# SHASwitch1.net
KiCad netlist of a schematic drawn in EAGLE
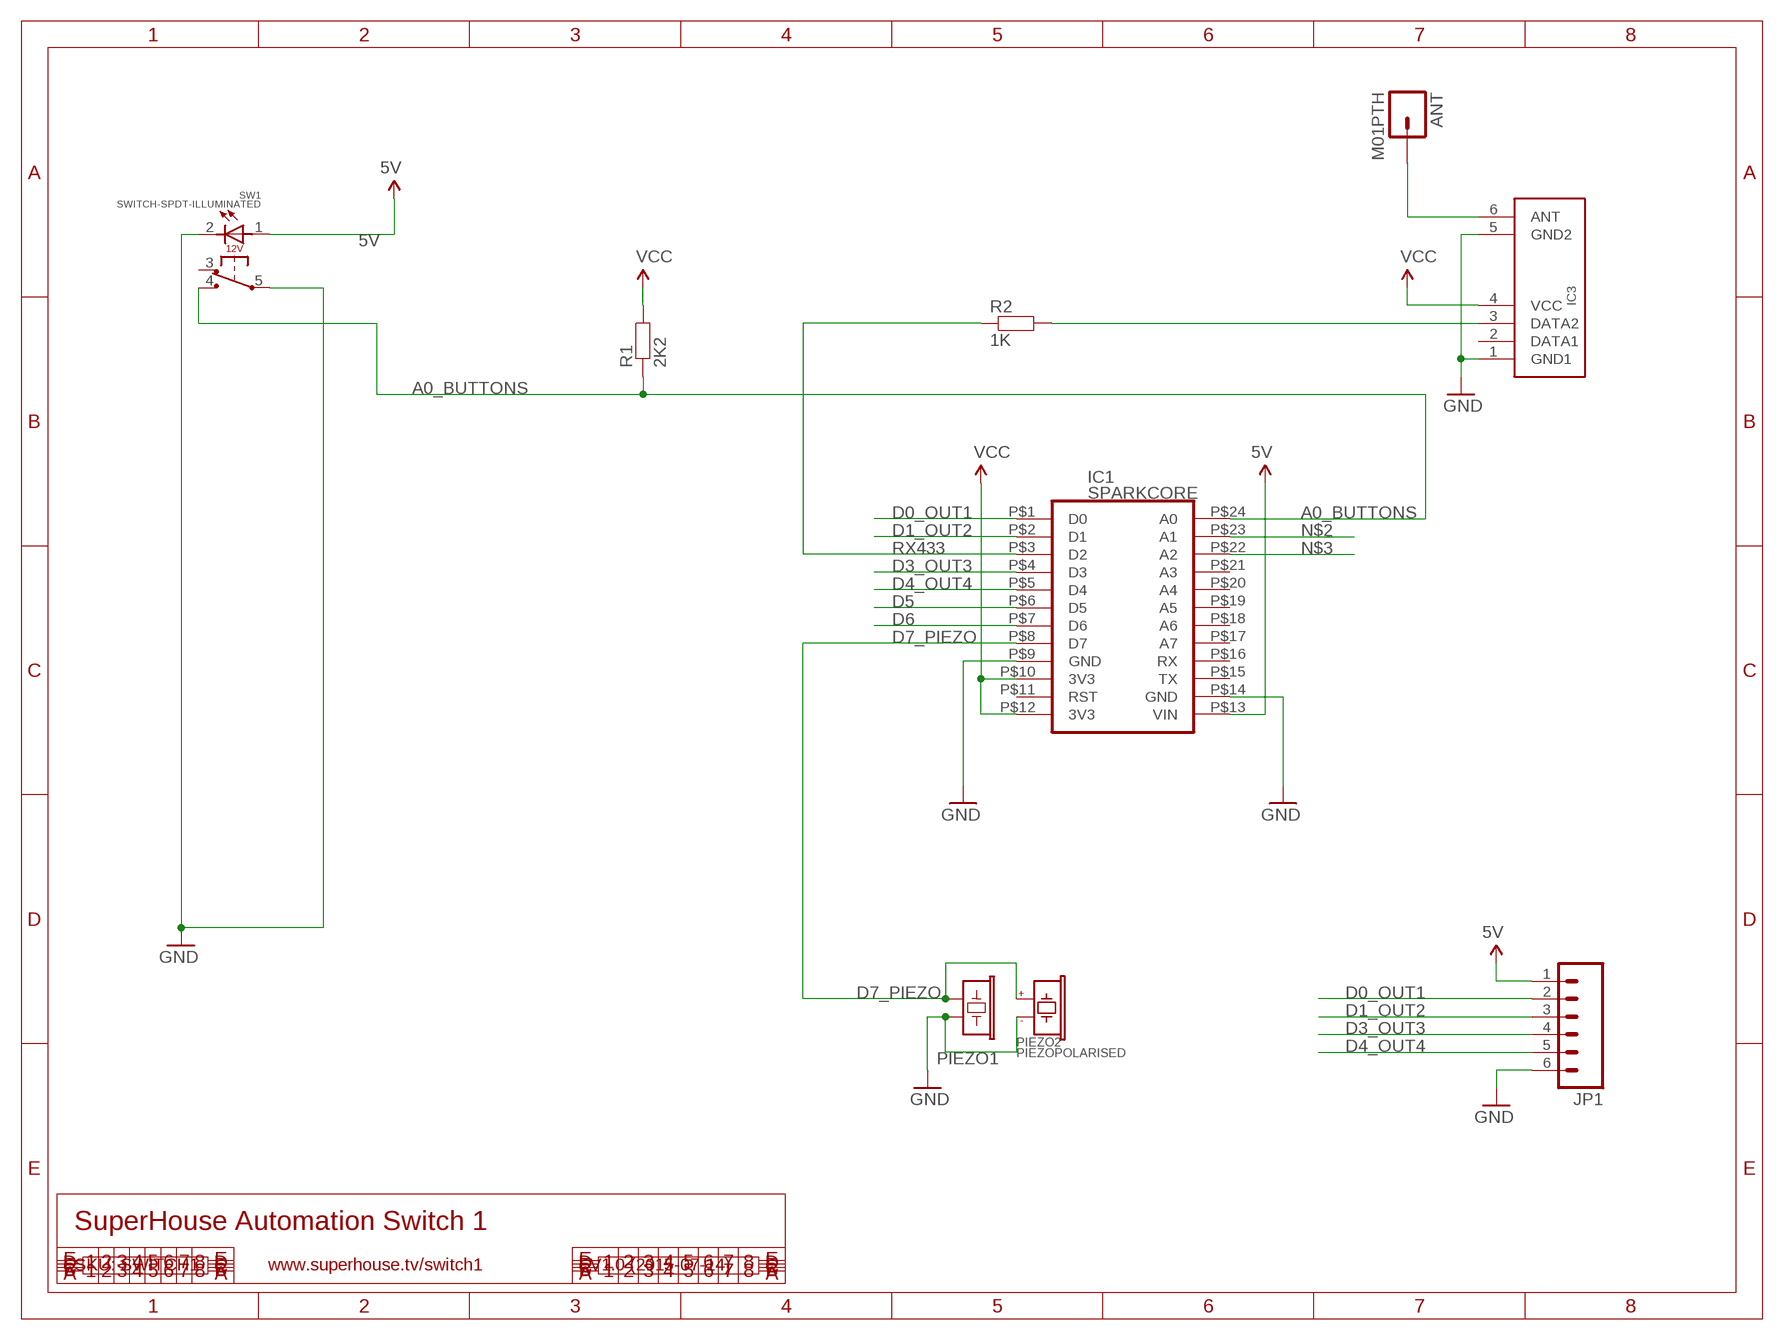
[diagram p0: schematic, sheet 1]

(export (version "E")
  (design (tool "Eeschema 10.0.6"))
  (components
    (comp (ref "ANT")
      (value "M01PTH")
      (footprint "eagle-import:1X01")
      (libsource (lib "eagle-import") (part "M01PTH"))
    )
    (comp (ref "IC1")
      (value "SPARKCORE")
      (footprint "eagle-import:SPARKCORE")
      (libsource (lib "eagle-import") (part "SPARKCORE"))
    )
    (comp (ref "IC3")
      (value "RXB1")
      (footprint "eagle-import:RX-B1-SHORT-FLAT")
      (libsource (lib "eagle-import") (part "RXB1SHORTFLAT"))
    )
    (comp (ref "JP1")
      (value "M06SIP")
      (footprint "eagle-import:1X06")
      (libsource (lib "eagle-import") (part "M06SIP"))
    )
    (comp (ref "PIEZO1")
      (value "BUZZERSMD12X12")
      (footprint "eagle-import:BUZZER-12X12-SMT")
      (libsource (lib "eagle-import") (part "BUZZERSMD12X12"))
    )
    (comp (ref "PIEZO2")
      (value "PIEZOPOLARISED")
      (footprint "eagle-import:PIEZO12MMWIDEPOLARISED")
      (libsource (lib "eagle-import") (part "PIEZOPOLARISED"))
    )
    (comp (ref "R1")
      (value "2K2")
      (footprint "eagle-import:0603")
      (libsource (lib "eagle-import") (part "RESISTOR0603"))
    )
    (comp (ref "R2")
      (value "1K")
      (footprint "eagle-import:0603")
      (libsource (lib "eagle-import") (part "RESISTOR0603"))
    )
    (comp (ref "SW1")
      (value "SWITCH-SPDT-ILLUMINATED")
      (footprint "eagle-import:SWITCH-SPDT-ILLUMINATED")
      (libsource (lib "eagle-import") (part "SWITCH-SPDT-ILLUMINATED"))
    )
  )
  (nets
    (net (code "1") (name "/A0_BUTTONS") (class "Default")
      (node (ref "IC1") (pin "P$24") (pinfunction "A0_P$24") (pintype "bidirectional"))
      (node (ref "R1") (pin "1") (pinfunction "1_1") (pintype "passive"))
      (node (ref "SW1") (pin "4") (pinfunction "NO_4") (pintype "passive"))
    )
    (net (code "2") (name "/D0_OUT1") (class "Default")
      (node (ref "IC1") (pin "P$1") (pinfunction "D0_P$1") (pintype "bidirectional"))
      (node (ref "JP1") (pin "2") (pinfunction "2_2") (pintype "passive"))
    )
    (net (code "3") (name "/D1_OUT2") (class "Default")
      (node (ref "IC1") (pin "P$2") (pinfunction "D1_P$2") (pintype "bidirectional"))
      (node (ref "JP1") (pin "3") (pinfunction "3_3") (pintype "passive"))
    )
    (net (code "4") (name "/D3_OUT3") (class "Default")
      (node (ref "IC1") (pin "P$4") (pinfunction "D3_P$4") (pintype "bidirectional"))
      (node (ref "JP1") (pin "4") (pinfunction "4_4") (pintype "passive"))
    )
    (net (code "5") (name "/D4_OUT4") (class "Default")
      (node (ref "IC1") (pin "P$5") (pinfunction "D4_P$5") (pintype "bidirectional"))
      (node (ref "JP1") (pin "5") (pinfunction "5_5") (pintype "passive"))
    )
    (net (code "6") (name "/D5") (class "Default")
      (node (ref "IC1") (pin "P$6") (pinfunction "D5_P$6") (pintype "bidirectional"))
    )
    (net (code "7") (name "/D6") (class "Default")
      (node (ref "IC1") (pin "P$7") (pinfunction "D6_P$7") (pintype "bidirectional"))
    )
    (net (code "8") (name "/D7_PIEZO") (class "Default")
      (node (ref "IC1") (pin "P$8") (pinfunction "D7_P$8") (pintype "bidirectional"))
      (node (ref "PIEZO1") (pin "1") (pinfunction "1_1") (pintype "passive"))
      (node (ref "PIEZO2") (pin "1") (pinfunction "+_1") (pintype "bidirectional"))
    )
    (net (code "9") (name "/N$2") (class "Default")
      (node (ref "IC1") (pin "P$23") (pinfunction "A1_P$23") (pintype "bidirectional"))
    )
    (net (code "10") (name "/N$3") (class "Default")
      (node (ref "IC1") (pin "P$22") (pinfunction "A2_P$22") (pintype "bidirectional"))
    )
    (net (code "11") (name "/RX433") (class "Default")
      (node (ref "IC1") (pin "P$3") (pinfunction "D2_P$3") (pintype "bidirectional"))
      (node (ref "R2") (pin "1") (pinfunction "1_1") (pintype "passive"))
    )
    (net (code "12") (name "5V") (class "Default")
      (node (ref "IC1") (pin "P$13") (pinfunction "VIN_P$13") (pintype "bidirectional"))
      (node (ref "JP1") (pin "1") (pinfunction "1_1") (pintype "passive"))
      (node (ref "SW1") (pin "1") (pinfunction "+_1") (pintype "passive"))
    )
    (net (code "13") (name "GND") (class "Default")
      (node (ref "IC1") (pin "P$14") (pinfunction "GND_P$14") (pintype "bidirectional"))
      (node (ref "IC1") (pin "P$9") (pinfunction "GND_P$9") (pintype "bidirectional"))
      (node (ref "IC3") (pin "1") (pinfunction "GND1_1") (pintype "bidirectional"))
      (node (ref "IC3") (pin "5") (pinfunction "GND2_5") (pintype "bidirectional"))
      (node (ref "JP1") (pin "6") (pinfunction "6_6") (pintype "passive"))
      (node (ref "PIEZO1") (pin "2") (pinfunction "2_2") (pintype "passive"))
      (node (ref "PIEZO2") (pin "2") (pinfunction "-_2") (pintype "bidirectional"))
      (node (ref "SW1") (pin "2") (pinfunction "-_2") (pintype "passive"))
      (node (ref "SW1") (pin "5") (pinfunction "COM_5") (pintype "passive"))
    )
    (net (code "14") (name "Net-(IC3-ANT)") (class "Default")
      (node (ref "ANT") (pin "1") (pinfunction "1_1") (pintype "passive"))
      (node (ref "IC3") (pin "6") (pinfunction "ANT_6") (pintype "bidirectional"))
    )
    (net (code "15") (name "Net-(IC3-DATA2)") (class "Default")
      (node (ref "IC3") (pin "3") (pinfunction "DATA2_3") (pintype "bidirectional"))
      (node (ref "R2") (pin "2") (pinfunction "2_2") (pintype "passive"))
    )
    (net (code "16") (name "VCC") (class "Default")
      (node (ref "IC1") (pin "P$10") (pinfunction "3V3_P$10") (pintype "bidirectional"))
      (node (ref "IC1") (pin "P$12") (pinfunction "3V3_P$12") (pintype "bidirectional"))
      (node (ref "IC3") (pin "4") (pinfunction "VCC_4") (pintype "bidirectional"))
      (node (ref "R1") (pin "2") (pinfunction "2_2") (pintype "passive"))
    )
    (net (code "17") (name "unconnected-(IC1-A3-PadP$21)") (class "Default")
      (node (ref "IC1") (pin "P$21") (pinfunction "A3_P$21") (pintype "bidirectional"))
    )
    (net (code "18") (name "unconnected-(IC1-A4-PadP$20)") (class "Default")
      (node (ref "IC1") (pin "P$20") (pinfunction "A4_P$20") (pintype "bidirectional"))
    )
    (net (code "19") (name "unconnected-(IC1-A5-PadP$19)") (class "Default")
      (node (ref "IC1") (pin "P$19") (pinfunction "A5_P$19") (pintype "bidirectional"))
    )
    (net (code "20") (name "unconnected-(IC1-A6-PadP$18)") (class "Default")
      (node (ref "IC1") (pin "P$18") (pinfunction "A6_P$18") (pintype "bidirectional"))
    )
    (net (code "21") (name "unconnected-(IC1-A7-PadP$17)") (class "Default")
      (node (ref "IC1") (pin "P$17") (pinfunction "A7_P$17") (pintype "bidirectional"))
    )
    (net (code "22") (name "unconnected-(IC1-RST-PadP$11)") (class "Default")
      (node (ref "IC1") (pin "P$11") (pinfunction "RST_P$11") (pintype "bidirectional"))
    )
    (net (code "23") (name "unconnected-(IC1-RX-PadP$16)") (class "Default")
      (node (ref "IC1") (pin "P$16") (pinfunction "RX_P$16") (pintype "bidirectional"))
    )
    (net (code "24") (name "unconnected-(IC1-TX-PadP$15)") (class "Default")
      (node (ref "IC1") (pin "P$15") (pinfunction "TX_P$15") (pintype "bidirectional"))
    )
    (net (code "25") (name "unconnected-(IC3-DATA1-Pad2)") (class "Default")
      (node (ref "IC3") (pin "2") (pinfunction "DATA1_2") (pintype "bidirectional"))
    )
    (net (code "26") (name "unconnected-(SW1-NC-Pad3)") (class "Default")
      (node (ref "SW1") (pin "3") (pinfunction "NC_3") (pintype "passive"))
    )
  )
)
